# Servos.net
KiCad netlist of a schematic drawn in Altium Designer
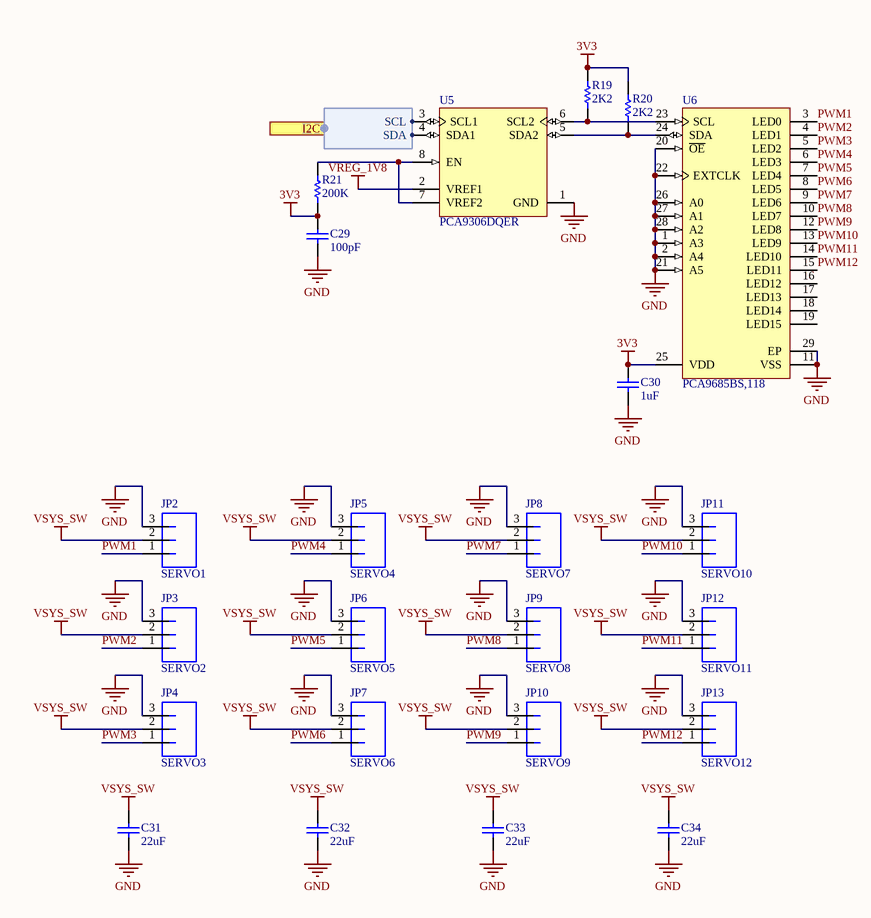
[diagram p0: Servos.SchDoc]

(export (version "E")
  (design (tool "Eeschema 10.0.6"))
  (components
    (comp (ref "C29")
      (value "100pF")
      (footprint "C0402[1005X55]")
      (description "100pF 100V 5% 0402 (1005 Metric)")
      (fields (field (name "PARTNUMBER") "GRM1555C2A101JA01D") (field (name "MANUFACTURER") "Murata"))
      (libsource (lib "Capacitors") (part "CAP_100pF_100V_0402_5%"))
    )
    (comp (ref "C30")
      (value "1uF")
      (footprint "C0402[1005X55]")
      (description "1uF 6.3V 10% 0402 (1005 Metric)")
      (fields (field (name "PARTNUMBER") "GRM155R70J105KA12D") (field (name "MANUFACTURER") "Murata"))
      (libsource (lib "Capacitors") (part "CAP_1uF_6.3V_0402_10%"))
    )
    (comp (ref "C31")
      (value "22uF")
      (footprint "C0603[1608X92]")
      (description "22uF 6.3V 10% 0603 (1608 Metric)")
      (fields (field (name "PARTNUMBER") "GRT188R60J226ME13D") (field (name "MANUFACTURER") "Murata"))
      (libsource (lib "Capacitors") (part "CAP_22uF_6.3V_0603_10%"))
    )
    (comp (ref "C32")
      (value "22uF")
      (footprint "C0603[1608X92]")
      (description "22uF 6.3V 10% 0603 (1608 Metric)")
      (fields (field (name "PARTNUMBER") "GRT188R60J226ME13D") (field (name "MANUFACTURER") "Murata"))
      (libsource (lib "Capacitors") (part "CAP_22uF_6.3V_0603_10%"))
    )
    (comp (ref "C33")
      (value "22uF")
      (footprint "C0603[1608X92]")
      (description "22uF 6.3V 10% 0603 (1608 Metric)")
      (fields (field (name "PARTNUMBER") "GRT188R60J226ME13D") (field (name "MANUFACTURER") "Murata"))
      (libsource (lib "Capacitors") (part "CAP_22uF_6.3V_0603_10%"))
    )
    (comp (ref "C34")
      (value "22uF")
      (footprint "C0603[1608X92]")
      (description "22uF 6.3V 10% 0603 (1608 Metric)")
      (fields (field (name "PARTNUMBER") "GRT188R60J226ME13D") (field (name "MANUFACTURER") "Murata"))
      (libsource (lib "Capacitors") (part "CAP_22uF_6.3V_0603_10%"))
    )
    (comp (ref "JP2")
      (value "SERVO1")
      (footprint "MOLEX-PICOBLADE-1.25MM-3-VERT-SMD")
      (fields (field (name "MANUFACTURER") "Molex") (field (name "PARTNUMBER") "0533980371"))
      (libsource (lib "Connectors") (part "MOLEX_PICOBLADE_1.25MM_3_VERT_SMD"))
    )
    (comp (ref "JP3")
      (value "SERVO2")
      (footprint "MOLEX-PICOBLADE-1.25MM-3-VERT-SMD")
      (fields (field (name "MANUFACTURER") "Molex") (field (name "PARTNUMBER") "0533980371"))
      (libsource (lib "Connectors") (part "MOLEX_PICOBLADE_1.25MM_3_VERT_SMD"))
    )
    (comp (ref "JP4")
      (value "SERVO3")
      (footprint "MOLEX-PICOBLADE-1.25MM-3-VERT-SMD")
      (fields (field (name "MANUFACTURER") "Molex") (field (name "PARTNUMBER") "0533980371"))
      (libsource (lib "Connectors") (part "MOLEX_PICOBLADE_1.25MM_3_VERT_SMD"))
    )
    (comp (ref "JP5")
      (value "SERVO4")
      (footprint "MOLEX-PICOBLADE-1.25MM-3-VERT-SMD")
      (fields (field (name "MANUFACTURER") "Molex") (field (name "PARTNUMBER") "0533980371"))
      (libsource (lib "Connectors") (part "MOLEX_PICOBLADE_1.25MM_3_VERT_SMD"))
    )
    (comp (ref "JP6")
      (value "SERVO5")
      (footprint "MOLEX-PICOBLADE-1.25MM-3-VERT-SMD")
      (fields (field (name "MANUFACTURER") "Molex") (field (name "PARTNUMBER") "0533980371"))
      (libsource (lib "Connectors") (part "MOLEX_PICOBLADE_1.25MM_3_VERT_SMD"))
    )
    (comp (ref "JP7")
      (value "SERVO6")
      (footprint "MOLEX-PICOBLADE-1.25MM-3-VERT-SMD")
      (fields (field (name "MANUFACTURER") "Molex") (field (name "PARTNUMBER") "0533980371"))
      (libsource (lib "Connectors") (part "MOLEX_PICOBLADE_1.25MM_3_VERT_SMD"))
    )
    (comp (ref "JP8")
      (value "SERVO7")
      (footprint "MOLEX-PICOBLADE-1.25MM-3-VERT-SMD")
      (fields (field (name "MANUFACTURER") "Molex") (field (name "PARTNUMBER") "0533980371"))
      (libsource (lib "Connectors") (part "MOLEX_PICOBLADE_1.25MM_3_VERT_SMD"))
    )
    (comp (ref "JP9")
      (value "SERVO8")
      (footprint "MOLEX-PICOBLADE-1.25MM-3-VERT-SMD")
      (fields (field (name "MANUFACTURER") "Molex") (field (name "PARTNUMBER") "0533980371"))
      (libsource (lib "Connectors") (part "MOLEX_PICOBLADE_1.25MM_3_VERT_SMD"))
    )
    (comp (ref "JP10")
      (value "SERVO9")
      (footprint "MOLEX-PICOBLADE-1.25MM-3-VERT-SMD")
      (fields (field (name "MANUFACTURER") "Molex") (field (name "PARTNUMBER") "0533980371"))
      (libsource (lib "Connectors") (part "MOLEX_PICOBLADE_1.25MM_3_VERT_SMD"))
    )
    (comp (ref "JP11")
      (value "SERVO10")
      (footprint "MOLEX-PICOBLADE-1.25MM-3-VERT-SMD")
      (fields (field (name "MANUFACTURER") "Molex") (field (name "PARTNUMBER") "0533980371"))
      (libsource (lib "Connectors") (part "MOLEX_PICOBLADE_1.25MM_3_VERT_SMD"))
    )
    (comp (ref "JP12")
      (value "SERVO11")
      (footprint "MOLEX-PICOBLADE-1.25MM-3-VERT-SMD")
      (fields (field (name "MANUFACTURER") "Molex") (field (name "PARTNUMBER") "0533980371"))
      (libsource (lib "Connectors") (part "MOLEX_PICOBLADE_1.25MM_3_VERT_SMD"))
    )
    (comp (ref "JP13")
      (value "SERVO12")
      (footprint "MOLEX-PICOBLADE-1.25MM-3-VERT-SMD")
      (fields (field (name "MANUFACTURER") "Molex") (field (name "PARTNUMBER") "0533980371"))
      (libsource (lib "Connectors") (part "MOLEX_PICOBLADE_1.25MM_3_VERT_SMD"))
    )
    (comp (ref "R19")
      (value "2K2")
      (footprint "R0402[1005]")
      (description "2K2 0.063W 1% 0402 (1005 Metric)")
      (fields (field (name "MANUFACTURER") "KOA Speer") (field (name "PARTNUMBER") "RK73H1ETTP2201F"))
      (libsource (lib "Resistors") (part "RES_2K2_0402_1%"))
    )
    (comp (ref "R20")
      (value "2K2")
      (footprint "R0402[1005]")
      (description "2K2 0.063W 1% 0402 (1005 Metric)")
      (fields (field (name "MANUFACTURER") "KOA Speer") (field (name "PARTNUMBER") "RK73H1ETTP2201F"))
      (libsource (lib "Resistors") (part "RES_2K2_0402_1%"))
    )
    (comp (ref "R21")
      (value "200K")
      (footprint "R0402[1005]")
      (description "200K 0.063W 1% 0402 (1005 Metric)")
      (fields (field (name "MANUFACTURER") "KOA Speer") (field (name "PARTNUMBER") "RK73H1ETTP2003F"))
      (libsource (lib "Resistors") (part "RES_200K_0402_1%"))
    )
    (comp (ref "U5")
      (value "PCA9306DQER")
      (footprint "DQE0008A_V")
      (fields (field (name "MANUFACTURER") "Texas Instruments"))
      (libsource (lib "Altium Content Vault") (part "TI-PCA9306-X2SON_DQE-8"))
    )
    (comp (ref "U6")
      (value "PCA9685BS,118")
      (footprint "VQFN-28")
      (description "IC LED DRVR LIN DIM 25MA 28HVQFN")
      (fields (field (name "MANUFACTURER") "NXP"))
      (libsource (lib "ICs") (part "PCA9685BS,118"))
    )
  )
  (nets
    (net (code "2") (name "/PWM1") (class "Default")
      (node (ref "JP2") (pin "1") (pinfunction "1_1") (pintype "passive"))
      (node (ref "U6") (pin "3") (pinfunction "LED0_3") (pintype "tri_state"))
    )
    (net (code "3") (name "/PWM2") (class "Default")
      (node (ref "JP3") (pin "1") (pinfunction "1_1") (pintype "passive"))
      (node (ref "U6") (pin "4") (pinfunction "LED1_4") (pintype "tri_state"))
    )
    (net (code "4") (name "/PWM3") (class "Default")
      (node (ref "JP4") (pin "1") (pinfunction "1_1") (pintype "passive"))
      (node (ref "U6") (pin "5") (pinfunction "LED2_5") (pintype "tri_state"))
    )
    (net (code "5") (name "/PWM4") (class "Default")
      (node (ref "JP5") (pin "1") (pinfunction "1_1") (pintype "passive"))
      (node (ref "U6") (pin "6") (pinfunction "LED3_6") (pintype "tri_state"))
    )
    (net (code "6") (name "/PWM5") (class "Default")
      (node (ref "JP6") (pin "1") (pinfunction "1_1") (pintype "passive"))
      (node (ref "U6") (pin "7") (pinfunction "LED4_7") (pintype "tri_state"))
    )
    (net (code "7") (name "/PWM6") (class "Default")
      (node (ref "JP7") (pin "1") (pinfunction "1_1") (pintype "passive"))
      (node (ref "U6") (pin "8") (pinfunction "LED5_8") (pintype "tri_state"))
    )
    (net (code "8") (name "/PWM7") (class "Default")
      (node (ref "JP8") (pin "1") (pinfunction "1_1") (pintype "passive"))
      (node (ref "U6") (pin "9") (pinfunction "LED6_9") (pintype "tri_state"))
    )
    (net (code "9") (name "/PWM8") (class "Default")
      (node (ref "JP9") (pin "1") (pinfunction "1_1") (pintype "passive"))
      (node (ref "U6") (pin "10") (pinfunction "LED7_10") (pintype "tri_state"))
    )
    (net (code "10") (name "/PWM9") (class "Default")
      (node (ref "JP10") (pin "1") (pinfunction "1_1") (pintype "passive"))
      (node (ref "U6") (pin "12") (pinfunction "LED8_12") (pintype "tri_state"))
    )
    (net (code "11") (name "/PWM10") (class "Default")
      (node (ref "JP11") (pin "1") (pinfunction "1_1") (pintype "passive"))
      (node (ref "U6") (pin "13") (pinfunction "LED9_13") (pintype "tri_state"))
    )
    (net (code "12") (name "/PWM11") (class "Default")
      (node (ref "JP12") (pin "1") (pinfunction "1_1") (pintype "passive"))
      (node (ref "U6") (pin "14") (pinfunction "LED10_14") (pintype "tri_state"))
    )
    (net (code "13") (name "/PWM12") (class "Default")
      (node (ref "JP13") (pin "1") (pinfunction "1_1") (pintype "passive"))
      (node (ref "U6") (pin "15") (pinfunction "LED11_15") (pintype "tri_state"))
    )
    (net (code "14") (name "/SCL") (class "Default")
      (node (ref "U5") (pin "3") (pinfunction "SCL1_3") (pintype "bidirectional"))
    )
    (net (code "15") (name "/SDA") (class "Default")
      (node (ref "U5") (pin "4") (pinfunction "SDA1_4") (pintype "bidirectional"))
    )
    (net (code "17") (name "3V3") (class "Default")
      (node (ref "C29") (pin "2") (pinfunction "2_2") (pintype "passive"))
      (node (ref "C30") (pin "2") (pinfunction "2_2") (pintype "passive"))
      (node (ref "R19") (pin "2") (pinfunction "2_2") (pintype "passive"))
      (node (ref "R20") (pin "2") (pinfunction "2_2") (pintype "passive"))
      (node (ref "R21") (pin "1") (pinfunction "1_1") (pintype "passive"))
      (node (ref "U6") (pin "25") (pinfunction "VDD_25") (pintype "power_in"))
    )
    (net (code "18") (name "GND") (class "Default")
      (node (ref "C29") (pin "1") (pinfunction "1_1") (pintype "passive"))
      (node (ref "C30") (pin "1") (pinfunction "1_1") (pintype "passive"))
      (node (ref "C31") (pin "1") (pinfunction "1_1") (pintype "passive"))
      (node (ref "C32") (pin "1") (pinfunction "1_1") (pintype "passive"))
      (node (ref "C33") (pin "1") (pinfunction "1_1") (pintype "passive"))
      (node (ref "C34") (pin "1") (pinfunction "1_1") (pintype "passive"))
      (node (ref "JP10") (pin "3") (pinfunction "3_3") (pintype "passive"))
      (node (ref "JP11") (pin "3") (pinfunction "3_3") (pintype "passive"))
      (node (ref "JP12") (pin "3") (pinfunction "3_3") (pintype "passive"))
      (node (ref "JP13") (pin "3") (pinfunction "3_3") (pintype "passive"))
      (node (ref "JP2") (pin "3") (pinfunction "3_3") (pintype "passive"))
      (node (ref "JP3") (pin "3") (pinfunction "3_3") (pintype "passive"))
      (node (ref "JP4") (pin "3") (pinfunction "3_3") (pintype "passive"))
      (node (ref "JP5") (pin "3") (pinfunction "3_3") (pintype "passive"))
      (node (ref "JP6") (pin "3") (pinfunction "3_3") (pintype "passive"))
      (node (ref "JP7") (pin "3") (pinfunction "3_3") (pintype "passive"))
      (node (ref "JP8") (pin "3") (pinfunction "3_3") (pintype "passive"))
      (node (ref "JP9") (pin "3") (pinfunction "3_3") (pintype "passive"))
      (node (ref "U5") (pin "1") (pinfunction "GND_1") (pintype "power_in"))
      (node (ref "U6") (pin "1") (pinfunction "A3_1") (pintype "input"))
      (node (ref "U6") (pin "11") (pinfunction "VSS_11") (pintype "power_in"))
      (node (ref "U6") (pin "2") (pinfunction "A4_2") (pintype "input"))
      (node (ref "U6") (pin "20") (pinfunction "~{OE}_20") (pintype "input"))
      (node (ref "U6") (pin "21") (pinfunction "A5_21") (pintype "input"))
      (node (ref "U6") (pin "22") (pinfunction "EXTCLK_22") (pintype "input"))
      (node (ref "U6") (pin "26") (pinfunction "A0_26") (pintype "input"))
      (node (ref "U6") (pin "27") (pinfunction "A1_27") (pintype "input"))
      (node (ref "U6") (pin "28") (pinfunction "A2_28") (pintype "input"))
      (node (ref "U6") (pin "29") (pinfunction "EP_29") (pintype "power_in"))
    )
    (net (code "19") (name "Net-(U5-EN)") (class "Default")
      (node (ref "R21") (pin "2") (pinfunction "2_2") (pintype "passive"))
      (node (ref "U5") (pin "7") (pinfunction "VREF2_7") (pintype "power_in"))
      (node (ref "U5") (pin "8") (pinfunction "EN_8") (pintype "input"))
    )
    (net (code "20") (name "Net-(U5-SCL2)") (class "Default")
      (node (ref "R19") (pin "1") (pinfunction "1_1") (pintype "passive"))
      (node (ref "U5") (pin "6") (pinfunction "SCL2_6") (pintype "bidirectional"))
      (node (ref "U6") (pin "23") (pinfunction "SCL_23") (pintype "input"))
    )
    (net (code "21") (name "Net-(U5-SDA2)") (class "Default")
      (node (ref "R20") (pin "1") (pinfunction "1_1") (pintype "passive"))
      (node (ref "U5") (pin "5") (pinfunction "SDA2_5") (pintype "bidirectional"))
      (node (ref "U6") (pin "24") (pinfunction "SDA_24") (pintype "bidirectional"))
    )
    (net (code "22") (name "VREG_1V8") (class "Default")
      (node (ref "U5") (pin "2") (pinfunction "VREF1_2") (pintype "power_in"))
    )
    (net (code "23") (name "VSYS_SW") (class "Default")
      (node (ref "C31") (pin "2") (pinfunction "2_2") (pintype "passive"))
      (node (ref "C32") (pin "2") (pinfunction "2_2") (pintype "passive"))
      (node (ref "C33") (pin "2") (pinfunction "2_2") (pintype "passive"))
      (node (ref "C34") (pin "2") (pinfunction "2_2") (pintype "passive"))
      (node (ref "JP10") (pin "2") (pinfunction "2_2") (pintype "passive"))
      (node (ref "JP11") (pin "2") (pinfunction "2_2") (pintype "passive"))
      (node (ref "JP12") (pin "2") (pinfunction "2_2") (pintype "passive"))
      (node (ref "JP13") (pin "2") (pinfunction "2_2") (pintype "passive"))
      (node (ref "JP2") (pin "2") (pinfunction "2_2") (pintype "passive"))
      (node (ref "JP3") (pin "2") (pinfunction "2_2") (pintype "passive"))
      (node (ref "JP4") (pin "2") (pinfunction "2_2") (pintype "passive"))
      (node (ref "JP5") (pin "2") (pinfunction "2_2") (pintype "passive"))
      (node (ref "JP6") (pin "2") (pinfunction "2_2") (pintype "passive"))
      (node (ref "JP7") (pin "2") (pinfunction "2_2") (pintype "passive"))
      (node (ref "JP8") (pin "2") (pinfunction "2_2") (pintype "passive"))
      (node (ref "JP9") (pin "2") (pinfunction "2_2") (pintype "passive"))
    )
    (net (code "24") (name "unconnected-(U6-LED12-Pad16)") (class "Default")
      (node (ref "U6") (pin "16") (pinfunction "LED12_16") (pintype "tri_state"))
    )
    (net (code "25") (name "unconnected-(U6-LED13-Pad17)") (class "Default")
      (node (ref "U6") (pin "17") (pinfunction "LED13_17") (pintype "tri_state"))
    )
    (net (code "26") (name "unconnected-(U6-LED14-Pad18)") (class "Default")
      (node (ref "U6") (pin "18") (pinfunction "LED14_18") (pintype "tri_state"))
    )
    (net (code "27") (name "unconnected-(U6-LED15-Pad19)") (class "Default")
      (node (ref "U6") (pin "19") (pinfunction "LED15_19") (pintype "tri_state"))
    )
  )
)
